# etherbotix_revB.net
KiCad netlist of a schematic drawn in EAGLE
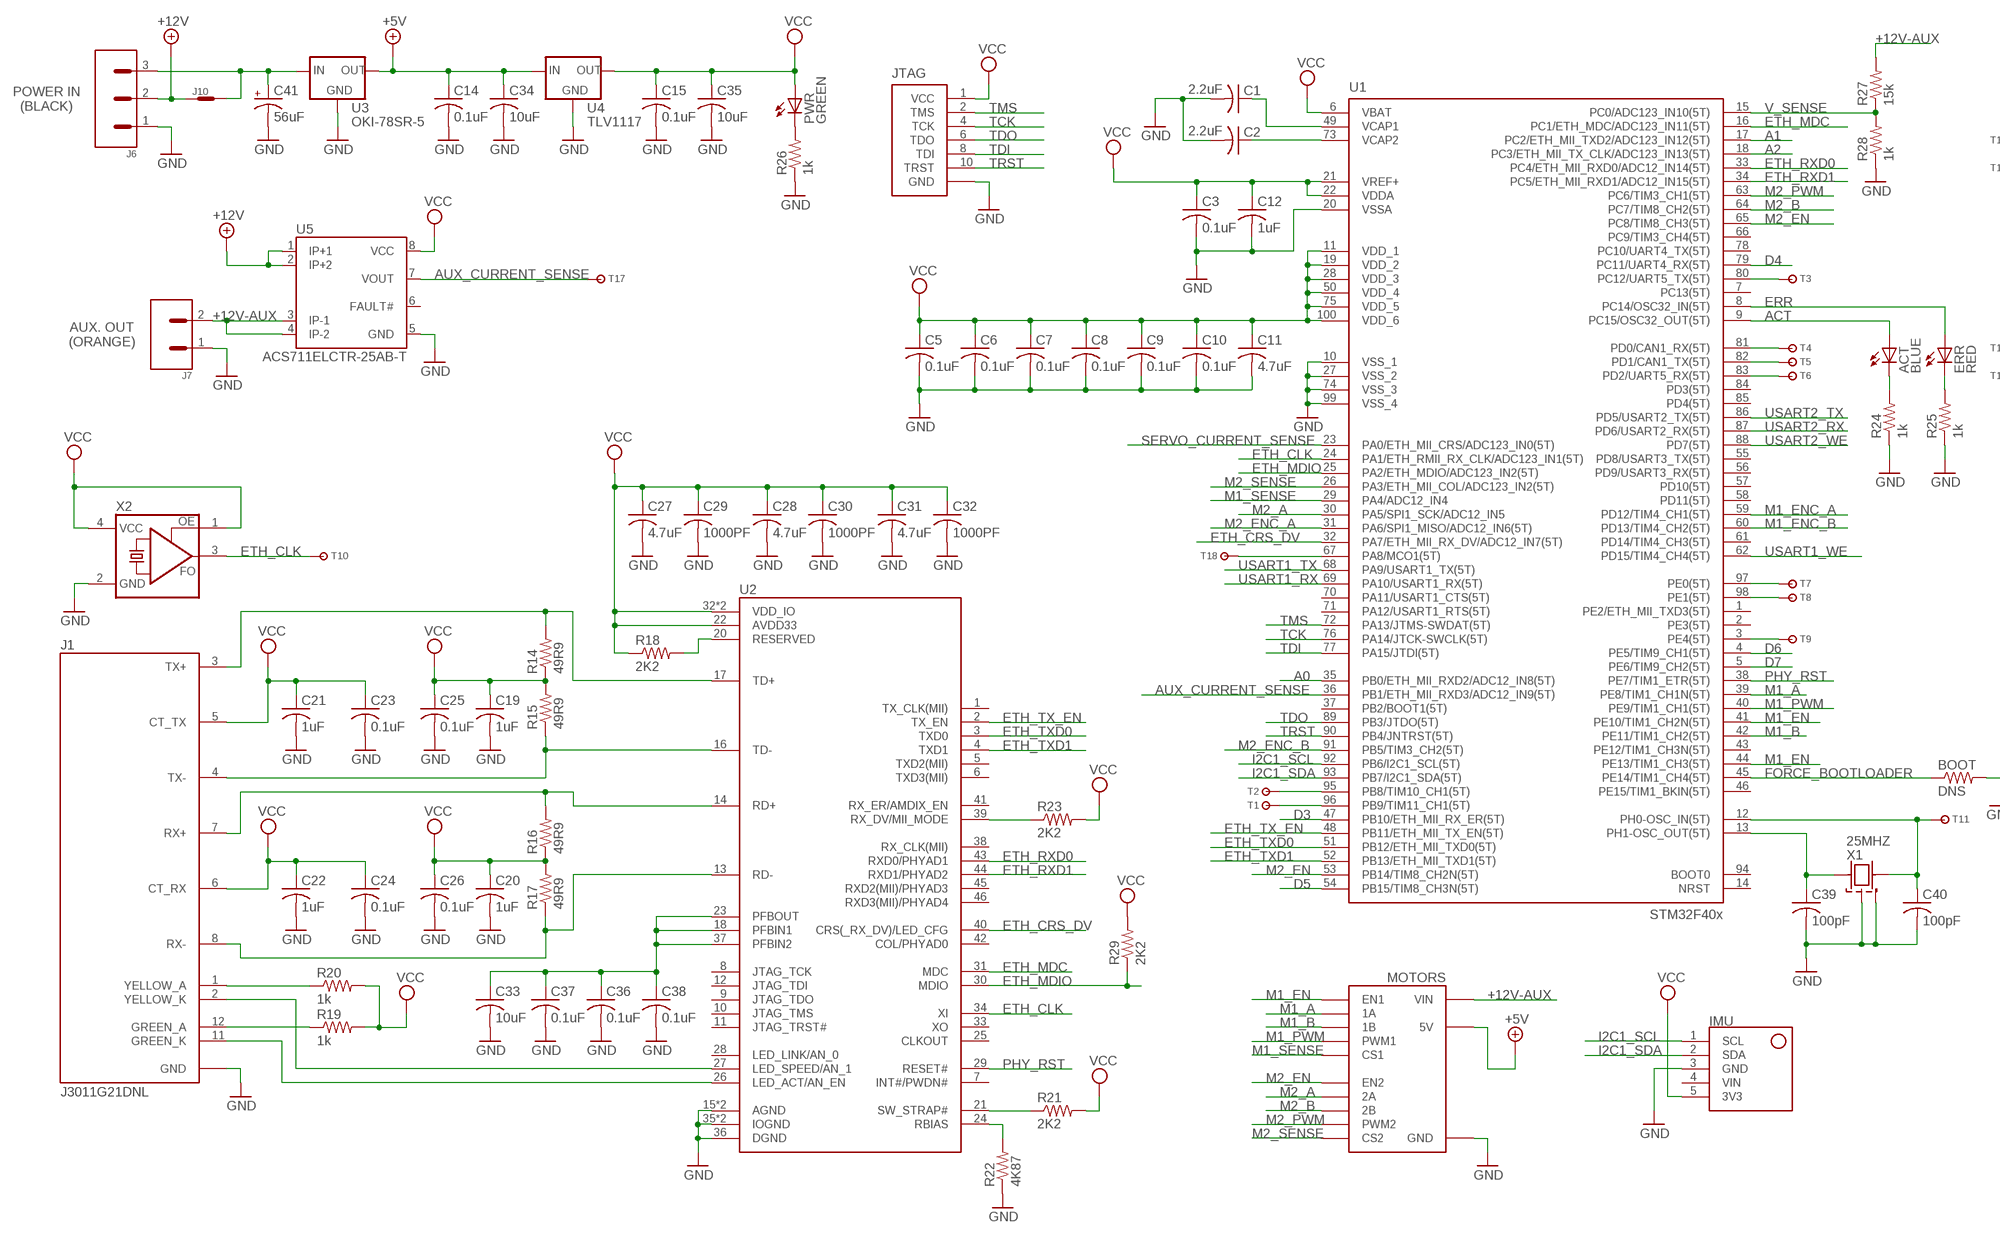
[diagram p0: schematic, sheet 1, part 1 of 2]
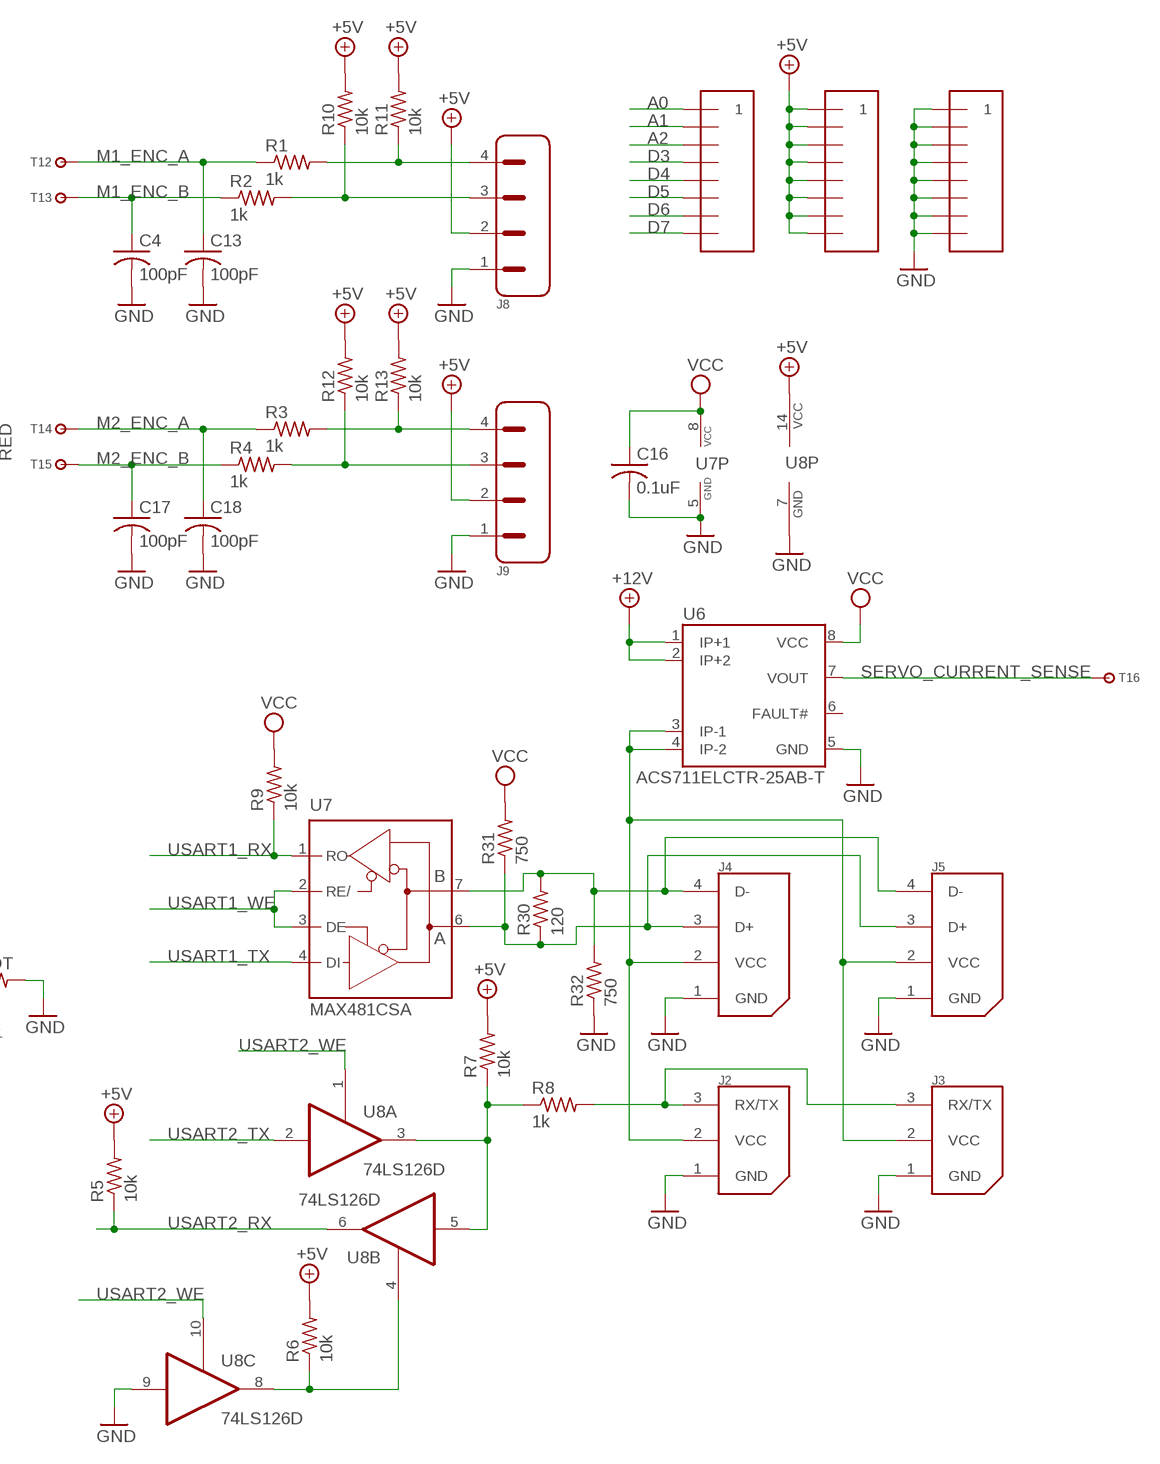
[diagram p1: schematic, sheet 1, part 2 of 2]

(export (version "E")
  (design (tool "Eeschema 10.0.6"))
  (components
    (comp (ref "ACT")
      (value "BLUE")
      (footprint "eagle-import:LED0603")
      (libsource (lib "eagle-import") (part "APT1608SGC"))
    )
    (comp (ref "BOOT")
      (value "DNS")
      (footprint "eagle-import:0603")
      (libsource (lib "eagle-import") (part "P1.00KHCT-ND"))
    )
    (comp (ref "C1")
      (value "2.2uF")
      (footprint "eagle-import:C0603")
      (libsource (lib "eagle-import") (part "C1608X5R1C225K"))
    )
    (comp (ref "C2")
      (value "2.2uF")
      (footprint "eagle-import:C0603")
      (libsource (lib "eagle-import") (part "C1608X5R1C225K"))
    )
    (comp (ref "C3")
      (value "0.1uF")
      (footprint "eagle-import:C0603")
      (libsource (lib "eagle-import") (part "C1608X7R1H104K"))
    )
    (comp (ref "C4")
      (value "100pF")
      (footprint "eagle-import:C0603")
      (libsource (lib "eagle-import") (part "C1608C0G1H101J"))
    )
    (comp (ref "C5")
      (value "0.1uF")
      (footprint "eagle-import:C0603")
      (libsource (lib "eagle-import") (part "C1608X7R1H104K"))
    )
    (comp (ref "C6")
      (value "0.1uF")
      (footprint "eagle-import:C0603")
      (libsource (lib "eagle-import") (part "C1608X7R1H104K"))
    )
    (comp (ref "C7")
      (value "0.1uF")
      (footprint "eagle-import:C0603")
      (libsource (lib "eagle-import") (part "C1608X7R1H104K"))
    )
    (comp (ref "C8")
      (value "0.1uF")
      (footprint "eagle-import:C0603")
      (libsource (lib "eagle-import") (part "C1608X7R1H104K"))
    )
    (comp (ref "C9")
      (value "0.1uF")
      (footprint "eagle-import:C0603")
      (libsource (lib "eagle-import") (part "C1608X7R1H104K"))
    )
    (comp (ref "C10")
      (value "0.1uF")
      (footprint "eagle-import:C0603")
      (libsource (lib "eagle-import") (part "C1608X7R1H104K"))
    )
    (comp (ref "C11")
      (value "4.7uF")
      (footprint "eagle-import:0603")
      (libsource (lib "eagle-import") (part "C1608X5R0J475K"))
    )
    (comp (ref "C12")
      (value "1uF")
      (footprint "eagle-import:C0603")
      (libsource (lib "eagle-import") (part "C1608X5R1H105M"))
    )
    (comp (ref "C13")
      (value "100pF")
      (footprint "eagle-import:C0603")
      (libsource (lib "eagle-import") (part "C1608C0G1H101J"))
    )
    (comp (ref "C14")
      (value "0.1uF")
      (footprint "eagle-import:C0603")
      (libsource (lib "eagle-import") (part "C1608X7R1H104K"))
    )
    (comp (ref "C15")
      (value "0.1uF")
      (footprint "eagle-import:C0603")
      (libsource (lib "eagle-import") (part "C1608X7R1H104K"))
    )
    (comp (ref "C16")
      (value "0.1uF")
      (footprint "eagle-import:C0603")
      (libsource (lib "eagle-import") (part "C1608X7R1H104K"))
    )
    (comp (ref "C17")
      (value "100pF")
      (footprint "eagle-import:C0603")
      (libsource (lib "eagle-import") (part "C1608C0G1H101J"))
    )
    (comp (ref "C18")
      (value "100pF")
      (footprint "eagle-import:C0603")
      (libsource (lib "eagle-import") (part "C1608C0G1H101J"))
    )
    (comp (ref "C19")
      (value "1uF")
      (footprint "eagle-import:C0603")
      (libsource (lib "eagle-import") (part "C1608X5R1H105M"))
    )
    (comp (ref "C20")
      (value "1uF")
      (footprint "eagle-import:C0603")
      (libsource (lib "eagle-import") (part "C1608X5R1H105M"))
    )
    (comp (ref "C21")
      (value "1uF")
      (footprint "eagle-import:C0603")
      (libsource (lib "eagle-import") (part "C1608X5R1H105M"))
    )
    (comp (ref "C22")
      (value "1uF")
      (footprint "eagle-import:C0603")
      (libsource (lib "eagle-import") (part "C1608X5R1H105M"))
    )
    (comp (ref "C23")
      (value "0.1uF")
      (footprint "eagle-import:C0603")
      (libsource (lib "eagle-import") (part "C1608X7R1H104K"))
    )
    (comp (ref "C24")
      (value "0.1uF")
      (footprint "eagle-import:C0603")
      (libsource (lib "eagle-import") (part "C1608X7R1H104K"))
    )
    (comp (ref "C25")
      (value "0.1uF")
      (footprint "eagle-import:C0603")
      (libsource (lib "eagle-import") (part "C1608X7R1H104K"))
    )
    (comp (ref "C26")
      (value "0.1uF")
      (footprint "eagle-import:C0603")
      (libsource (lib "eagle-import") (part "C1608X7R1H104K"))
    )
    (comp (ref "C27")
      (value "4.7uF")
      (footprint "eagle-import:0603")
      (libsource (lib "eagle-import") (part "C1608X5R0J475K"))
    )
    (comp (ref "C28")
      (value "4.7uF")
      (footprint "eagle-import:0603")
      (libsource (lib "eagle-import") (part "C1608X5R0J475K"))
    )
    (comp (ref "C29")
      (value "1000PF")
      (footprint "eagle-import:0603")
      (libsource (lib "eagle-import") (part "C1608X7R1H102K"))
    )
    (comp (ref "C30")
      (value "1000PF")
      (footprint "eagle-import:0603")
      (libsource (lib "eagle-import") (part "C1608X7R1H102K"))
    )
    (comp (ref "C31")
      (value "4.7uF")
      (footprint "eagle-import:0603")
      (libsource (lib "eagle-import") (part "C1608X5R0J475K"))
    )
    (comp (ref "C32")
      (value "1000PF")
      (footprint "eagle-import:0603")
      (libsource (lib "eagle-import") (part "C1608X7R1H102K"))
    )
    (comp (ref "C33")
      (value "10uF")
      (footprint "eagle-import:C0603")
      (libsource (lib "eagle-import") (part "C1608X5R0J106M"))
    )
    (comp (ref "C34")
      (value "10uF")
      (footprint "eagle-import:C0603")
      (libsource (lib "eagle-import") (part "C1608X5R0J106M"))
    )
    (comp (ref "C35")
      (value "10uF")
      (footprint "eagle-import:C0603")
      (libsource (lib "eagle-import") (part "C1608X5R0J106M"))
    )
    (comp (ref "C36")
      (value "0.1uF")
      (footprint "eagle-import:C0603")
      (libsource (lib "eagle-import") (part "C1608X7R1H104K"))
    )
    (comp (ref "C37")
      (value "0.1uF")
      (footprint "eagle-import:C0603")
      (libsource (lib "eagle-import") (part "C1608X7R1H104K"))
    )
    (comp (ref "C38")
      (value "0.1uF")
      (footprint "eagle-import:C0603")
      (libsource (lib "eagle-import") (part "C1608X7R1H104K"))
    )
    (comp (ref "C39")
      (value "100pF")
      (footprint "eagle-import:C0603")
      (libsource (lib "eagle-import") (part "C1608C0G1H101J"))
    )
    (comp (ref "C40")
      (value "100pF")
      (footprint "eagle-import:C0603")
      (libsource (lib "eagle-import") (part "C1608C0G1H101J"))
    )
    (comp (ref "C41")
      (value "56uF")
      (footprint "eagle-import:OSCON_SVPF_6.3MM")
      (libsource (lib "eagle-import") (part "25SVPF56M"))
    )
    (comp (ref "ERR")
      (value "RED")
      (footprint "eagle-import:LED0603")
      (libsource (lib "eagle-import") (part "APT1608SGC"))
    )
    (comp (ref "IMU")
      (value "MINI9IMU")
      (footprint "eagle-import:MINI9IMU")
      (libsource (lib "eagle-import") (part "MINI9IMU"))
    )
    (comp (ref "J1")
      (value "J3011G21DNL")
      (footprint "eagle-import:J3")
      (libsource (lib "eagle-import") (part "J3011G21DNL"))
    )
    (comp (ref "J2")
      (value "22-03-5035")
      (footprint "eagle-import:5267-3")
      (libsource (lib "eagle-import") (part "22-03-5035"))
    )
    (comp (ref "J3")
      (value "22-03-5035")
      (footprint "eagle-import:5267-3")
      (libsource (lib "eagle-import") (part "22-03-5035"))
    )
    (comp (ref "J4")
      (value "22-03-5045")
      (footprint "eagle-import:5267-4")
      (libsource (lib "eagle-import") (part "22-03-5045"))
    )
    (comp (ref "J5")
      (value "22-03-5045")
      (footprint "eagle-import:5267-4")
      (libsource (lib "eagle-import") (part "22-03-5045"))
    )
    (comp (ref "J6")
      (value "1760520000")
      (footprint "eagle-import:1760520000")
      (libsource (lib "eagle-import") (part "1760520000"))
    )
    (comp (ref "J7")
      (value "1760490000")
      (footprint "eagle-import:1760490000")
      (libsource (lib "eagle-import") (part "1760490000"))
    )
    (comp (ref "J8")
      (value "502443-0470")
      (footprint "eagle-import:502443-0470")
      (libsource (lib "eagle-import") (part "502443-0470"))
    )
    (comp (ref "J9")
      (value "502443-0470")
      (footprint "eagle-import:502443-0470")
      (libsource (lib "eagle-import") (part "502443-0470"))
    )
    (comp (ref "J10")
      (value "JUMPER")
      (footprint "eagle-import:J2")
      (libsource (lib "eagle-import") (part "JUMPER"))
    )
    (comp (ref "JTAG")
      (value "CORTEX_DEBUG-SHROUDED")
      (footprint "eagle-import:3220-10-0300-00")
      (libsource (lib "eagle-import") (part "CORTEX_DEBUG-SHROUDED"))
    )
    (comp (ref "MOTORS")
      (value "MD03A")
      (footprint "eagle-import:MD03A")
      (libsource (lib "eagle-import") (part "MD03A"))
    )
    (comp (ref "PWR")
      (value "GREEN")
      (footprint "eagle-import:LED0603")
      (libsource (lib "eagle-import") (part "APT1608SGC"))
    )
    (comp (ref "R1")
      (value "1k")
      (footprint "eagle-import:0603")
      (libsource (lib "eagle-import") (part "P1.00KHCT-ND"))
    )
    (comp (ref "R2")
      (value "1k")
      (footprint "eagle-import:0603")
      (libsource (lib "eagle-import") (part "P1.00KHCT-ND"))
    )
    (comp (ref "R3")
      (value "1k")
      (footprint "eagle-import:0603")
      (libsource (lib "eagle-import") (part "P1.00KHCT-ND"))
    )
    (comp (ref "R4")
      (value "1k")
      (footprint "eagle-import:0603")
      (libsource (lib "eagle-import") (part "P1.00KHCT-ND"))
    )
    (comp (ref "R5")
      (value "10k")
      (footprint "eagle-import:0603")
      (libsource (lib "eagle-import") (part "P10.0KHCT-ND"))
    )
    (comp (ref "R6")
      (value "10k")
      (footprint "eagle-import:0603")
      (libsource (lib "eagle-import") (part "P10.0KHCT-ND"))
    )
    (comp (ref "R7")
      (value "10k")
      (footprint "eagle-import:0603")
      (libsource (lib "eagle-import") (part "P10.0KHCT-ND"))
    )
    (comp (ref "R8")
      (value "1k")
      (footprint "eagle-import:0603")
      (libsource (lib "eagle-import") (part "P1.00KHCT-ND"))
    )
    (comp (ref "R9")
      (value "10k")
      (footprint "eagle-import:0603")
      (libsource (lib "eagle-import") (part "P10.0KHCT-ND"))
    )
    (comp (ref "R10")
      (value "10k")
      (footprint "eagle-import:0603")
      (libsource (lib "eagle-import") (part "P10.0KHCT-ND"))
    )
    (comp (ref "R11")
      (value "10k")
      (footprint "eagle-import:0603")
      (libsource (lib "eagle-import") (part "P10.0KHCT-ND"))
    )
    (comp (ref "R12")
      (value "10k")
      (footprint "eagle-import:0603")
      (libsource (lib "eagle-import") (part "P10.0KHCT-ND"))
    )
    (comp (ref "R13")
      (value "10k")
      (footprint "eagle-import:0603")
      (libsource (lib "eagle-import") (part "P10.0KHCT-ND"))
    )
    (comp (ref "R14")
      (value "49R9")
      (footprint "eagle-import:0603")
      (libsource (lib "eagle-import") (part "P49.9HCT-ND"))
    )
    (comp (ref "R15")
      (value "49R9")
      (footprint "eagle-import:0603")
      (libsource (lib "eagle-import") (part "P49.9HCT-ND"))
    )
    (comp (ref "R16")
      (value "49R9")
      (footprint "eagle-import:0603")
      (libsource (lib "eagle-import") (part "P49.9HCT-ND"))
    )
    (comp (ref "R17")
      (value "49R9")
      (footprint "eagle-import:0603")
      (libsource (lib "eagle-import") (part "P49.9HCT-ND"))
    )
    (comp (ref "R18")
      (value "2K2")
      (footprint "eagle-import:0603")
      (libsource (lib "eagle-import") (part "P2.20KHCT-ND"))
    )
    (comp (ref "R19")
      (value "1k")
      (footprint "eagle-import:0603")
      (libsource (lib "eagle-import") (part "P1.00KHCT-ND"))
    )
    (comp (ref "R20")
      (value "1k")
      (footprint "eagle-import:0603")
      (libsource (lib "eagle-import") (part "P1.00KHCT-ND"))
    )
    (comp (ref "R21")
      (value "2K2")
      (footprint "eagle-import:0603")
      (libsource (lib "eagle-import") (part "P2.20KHCT-ND"))
    )
    (comp (ref "R22")
      (value "4K87")
      (footprint "eagle-import:0603")
      (libsource (lib "eagle-import") (part "P4.87KHCT-ND"))
    )
    (comp (ref "R23")
      (value "2K2")
      (footprint "eagle-import:0603")
      (libsource (lib "eagle-import") (part "P2.20KHCT-ND"))
    )
    (comp (ref "R24")
      (value "1k")
      (footprint "eagle-import:0603")
      (libsource (lib "eagle-import") (part "P1.00KHCT-ND"))
    )
    (comp (ref "R25")
      (value "1k")
      (footprint "eagle-import:0603")
      (libsource (lib "eagle-import") (part "P1.00KHCT-ND"))
    )
    (comp (ref "R26")
      (value "1k")
      (footprint "eagle-import:0603")
      (libsource (lib "eagle-import") (part "P1.00KHCT-ND"))
    )
    (comp (ref "R27")
      (value "15k")
      (footprint "eagle-import:0603")
      (libsource (lib "eagle-import") (part "P15.0KHCT-ND"))
    )
    (comp (ref "R28")
      (value "1k")
      (footprint "eagle-import:0603")
      (libsource (lib "eagle-import") (part "P1.00KHCT-ND"))
    )
    (comp (ref "R29")
      (value "2K2")
      (footprint "eagle-import:0603")
      (libsource (lib "eagle-import") (part "P2.20KHCT-ND"))
    )
    (comp (ref "R30")
      (value "120")
      (footprint "eagle-import:0603")
      (libsource (lib "eagle-import") (part "P120HCT-ND"))
    )
    (comp (ref "R31")
      (value "750")
      (footprint "eagle-import:0603")
      (libsource (lib "eagle-import") (part "P750HCT-ND"))
    )
    (comp (ref "R32")
      (value "750")
      (footprint "eagle-import:0603")
      (libsource (lib "eagle-import") (part "P750HCT-ND"))
    )
    (comp (ref "T1")
      (value "TESTPAD")
      (footprint "eagle-import:TEST")
      (libsource (lib "eagle-import") (part "TESTPAD"))
    )
    (comp (ref "T2")
      (value "TESTPAD")
      (footprint "eagle-import:TEST")
      (libsource (lib "eagle-import") (part "TESTPAD"))
    )
    (comp (ref "T3")
      (value "TESTPAD")
      (footprint "eagle-import:TEST")
      (libsource (lib "eagle-import") (part "TESTPAD"))
    )
    (comp (ref "T4")
      (value "TESTPAD")
      (footprint "eagle-import:TEST")
      (libsource (lib "eagle-import") (part "TESTPAD"))
    )
    (comp (ref "T5")
      (value "TESTPAD")
      (footprint "eagle-import:TEST")
      (libsource (lib "eagle-import") (part "TESTPAD"))
    )
    (comp (ref "T6")
      (value "TESTPAD")
      (footprint "eagle-import:TEST")
      (libsource (lib "eagle-import") (part "TESTPAD"))
    )
    (comp (ref "T7")
      (value "TESTPAD")
      (footprint "eagle-import:TEST")
      (libsource (lib "eagle-import") (part "TESTPAD"))
    )
    (comp (ref "T8")
      (value "TESTPAD")
      (footprint "eagle-import:TEST")
      (libsource (lib "eagle-import") (part "TESTPAD"))
    )
    (comp (ref "T9")
      (value "TESTPAD")
      (footprint "eagle-import:TEST")
      (libsource (lib "eagle-import") (part "TESTPAD"))
    )
    (comp (ref "T10")
      (value "TESTPAD")
      (footprint "eagle-import:TEST")
      (libsource (lib "eagle-import") (part "TESTPAD"))
    )
    (comp (ref "T11")
      (value "TESTPAD")
      (footprint "eagle-import:TEST")
      (libsource (lib "eagle-import") (part "TESTPAD"))
    )
    (comp (ref "T12")
      (value "TESTPAD")
      (footprint "eagle-import:TEST")
      (libsource (lib "eagle-import") (part "TESTPAD"))
    )
    (comp (ref "T13")
      (value "TESTPAD")
      (footprint "eagle-import:TEST")
      (libsource (lib "eagle-import") (part "TESTPAD"))
    )
    (comp (ref "T14")
      (value "TESTPAD")
      (footprint "eagle-import:TEST")
      (libsource (lib "eagle-import") (part "TESTPAD"))
    )
    (comp (ref "T15")
      (value "TESTPAD")
      (footprint "eagle-import:TEST")
      (libsource (lib "eagle-import") (part "TESTPAD"))
    )
    (comp (ref "T16")
      (value "TESTPAD")
      (footprint "eagle-import:TEST")
      (libsource (lib "eagle-import") (part "TESTPAD"))
    )
    (comp (ref "T17")
      (value "TESTPAD")
      (footprint "eagle-import:TEST")
      (libsource (lib "eagle-import") (part "TESTPAD"))
    )
    (comp (ref "T18")
      (value "TESTPAD")
      (footprint "eagle-import:TEST")
      (libsource (lib "eagle-import") (part "TESTPAD"))
    )
    (comp (ref "U$1")
      (value "HEADER8")
      (footprint "eagle-import:1X8")
      (libsource (lib "eagle-import") (part "HEADER8"))
    )
    (comp (ref "U$2")
      (value "HEADER8")
      (footprint "eagle-import:1X8")
      (libsource (lib "eagle-import") (part "HEADER8"))
    )
    (comp (ref "U$3")
      (value "HEADER8")
      (footprint "eagle-import:1X8")
      (libsource (lib "eagle-import") (part "HEADER8"))
    )
    (comp (ref "U1")
      (value "STM32F407V")
      (footprint "eagle-import:TQFP100")
      (libsource (lib "eagle-import") (part "STM32F407V"))
    )
    (comp (ref "U2")
      (value "TLK110")
      (footprint "eagle-import:LQFP48")
      (libsource (lib "eagle-import") (part "TLK110"))
    )
    (comp (ref "U3")
      (value "OKI-78SR-5")
      (footprint "eagle-import:OKI-78SR")
      (fields (field (name "VOLTAGE") "5"))
      (libsource (lib "eagle-import") (part "OKI-78SR-W36-C-5/1.5"))
    )
    (comp (ref "U4")
      (value "TLV1117")
      (footprint "eagle-import:DPAK")
      (libsource (lib "eagle-import") (part "TLV1117-33IKVURG3KVU"))
    )
    (comp (ref "U5")
      (value "ACS711ELCTR-25AB-T")
      (footprint "eagle-import:SOIC8")
      (libsource (lib "eagle-import") (part "ACS711ELC?TR-25AB-T"))
    )
    (comp (ref "U6")
      (value "ACS711ELCTR-25AB-T")
      (footprint "eagle-import:SOIC8")
      (libsource (lib "eagle-import") (part "ACS711ELC?TR-25AB-T"))
    )
    (comp (ref "U7")
      (value "MAX481CSA")
      (footprint "eagle-import:SO08")
      (fields (field (name "MF") "MAXIM"))
      (libsource (lib "eagle-import") (part "MAX481CSA"))
    )
    (comp (ref "U8")
      (value "74LS126D")
      (footprint "eagle-import:SO14")
      (libsource (lib "eagle-import") (part "74126DLS"))
    )
    (comp (ref "X1")
      (value "25MHZ")
      (footprint "eagle-import:4LCC")
      (libsource (lib "eagle-import") (part "ABM3B-MHZ-B2-T25.000"))
    )
    (comp (ref "X2")
      (value "ASEMB-50.000MHZ-XY-T")
      (footprint "eagle-import:OSCILLATOR")
      (libsource (lib "eagle-import") (part "ASEMB-50.000MHZ-XY-T"))
    )
  )
  (nets
    (net (code "1") (name "+5V") (class "Default")
      (node (ref "C14") (pin "1") (pinfunction "1_1") (pintype "passive"))
      (node (ref "C34") (pin "1") (pinfunction "1_1") (pintype "passive"))
      (node (ref "J8") (pin "2") (pinfunction "2_2") (pintype "bidirectional"))
      (node (ref "J9") (pin "2") (pinfunction "2_2") (pintype "bidirectional"))
      (node (ref "MOTORS") (pin "5V") (pinfunction "5V_5V") (pintype "bidirectional"))
      (node (ref "R10") (pin "2") (pinfunction "2_2") (pintype "passive"))
      (node (ref "R11") (pin "2") (pinfunction "2_2") (pintype "passive"))
      (node (ref "R12") (pin "2") (pinfunction "2_2") (pintype "passive"))
      (node (ref "R13") (pin "2") (pinfunction "2_2") (pintype "passive"))
      (node (ref "R5") (pin "2") (pinfunction "2_2") (pintype "passive"))
      (node (ref "R6") (pin "2") (pinfunction "2_2") (pintype "passive"))
      (node (ref "R7") (pin "2") (pinfunction "2_2") (pintype "passive"))
      (node (ref "U$2") (pin "P$1") (pinfunction "1_P$1") (pintype "bidirectional"))
      (node (ref "U$2") (pin "P$2") (pinfunction "P$2_P$2") (pintype "bidirectional"))
      (node (ref "U$2") (pin "P$3") (pinfunction "P$3_P$3") (pintype "bidirectional"))
      (node (ref "U$2") (pin "P$4") (pinfunction "P$4_P$4") (pintype "bidirectional"))
      (node (ref "U$2") (pin "P$5") (pinfunction "P$5_P$5") (pintype "bidirectional"))
      (node (ref "U$2") (pin "P$6") (pinfunction "P$6_P$6") (pintype "bidirectional"))
      (node (ref "U$2") (pin "P$7") (pinfunction "P$7_P$7") (pintype "bidirectional"))
      (node (ref "U$2") (pin "P$8") (pinfunction "P$8_P$8") (pintype "bidirectional"))
      (node (ref "U3") (pin "P$3") (pinfunction "OUT_P$3") (pintype "passive"))
      (node (ref "U4") (pin "3") (pinfunction "IN_3") (pintype "input"))
      (node (ref "U8") (pin "14") (pinfunction "VCC_14") (pintype "power_in"))
    )
    (net (code "2") (name "+12V") (class "Default")
      (node (ref "J10") (pin "A") (pinfunction "A_A") (pintype "bidirectional"))
      (node (ref "J6") (pin "2") (pinfunction "2_2") (pintype "bidirectional"))
      (node (ref "U5") (pin "1") (pinfunction "IP+1_1") (pintype "bidirectional"))
      (node (ref "U5") (pin "2") (pinfunction "IP+2_2") (pintype "bidirectional"))
      (node (ref "U6") (pin "1") (pinfunction "IP+1_1") (pintype "bidirectional"))
      (node (ref "U6") (pin "2") (pinfunction "IP+2_2") (pintype "bidirectional"))
    )
    (net (code "3") (name "/+12V-AUX") (class "Default")
      (node (ref "J7") (pin "2") (pinfunction "2_2") (pintype "bidirectional"))
      (node (ref "MOTORS") (pin "VIN1") (pinfunction "VIN_VIN1") (pintype "bidirectional"))
      (node (ref "MOTORS") (pin "VIN2") (pinfunction "VIN_VIN2") (pintype "bidirectional"))
      (node (ref "R27") (pin "2") (pinfunction "2_2") (pintype "passive"))
      (node (ref "U5") (pin "3") (pinfunction "IP-1_3") (pintype "bidirectional"))
      (node (ref "U5") (pin "4") (pinfunction "IP-2_4") (pintype "bidirectional"))
    )
    (net (code "4") (name "/A0") (class "Default")
      (node (ref "U$1") (pin "P$1") (pinfunction "1_P$1") (pintype "bidirectional"))
      (node (ref "U1") (pin "35") (pinfunction "PB0/ETH_MII_RXD2/ADC12_IN8(5T)_35") (pintype "bidirectional"))
    )
    (net (code "5") (name "/A1") (class "Default")
      (node (ref "U$1") (pin "P$2") (pinfunction "P$2_P$2") (pintype "bidirectional"))
      (node (ref "U1") (pin "17") (pinfunction "PC2/ETH_MII_TXD2/ADC123_IN12(5T)_17") (pintype "bidirectional"))
    )
    (net (code "6") (name "/A2") (class "Default")
      (node (ref "U$1") (pin "P$3") (pinfunction "P$3_P$3") (pintype "bidirectional"))
      (node (ref "U1") (pin "18") (pinfunction "PC3/ETH_MII_TX_CLK/ADC123_IN13(5T)_18") (pintype "bidirectional"))
    )
    (net (code "7") (name "/ACT") (class "Default")
      (node (ref "ACT") (pin "A") (pinfunction "A_A") (pintype "passive"))
      (node (ref "U1") (pin "9") (pinfunction "PC15/OSC32_OUT(5T)_9") (pintype "bidirectional"))
    )
    (net (code "8") (name "/AUX_CURRENT_SENSE") (class "Default")
      (node (ref "T17") (pin "T") (pinfunction "1_T") (pintype "bidirectional"))
      (node (ref "U1") (pin "36") (pinfunction "PB1/ETH_MII_RXD3/ADC12_IN9(5T)_36") (pintype "bidirectional"))
      (node (ref "U5") (pin "7") (pinfunction "VOUT_7") (pintype "bidirectional"))
    )
    (net (code "9") (name "/D3") (class "Default")
      (node (ref "U$1") (pin "P$4") (pinfunction "P$4_P$4") (pintype "bidirectional"))
      (node (ref "U1") (pin "47") (pinfunction "PB10/ETH_MII_RX_ER(5T)_47") (pintype "bidirectional"))
    )
    (net (code "10") (name "/D4") (class "Default")
      (node (ref "U$1") (pin "P$5") (pinfunction "P$5_P$5") (pintype "bidirectional"))
      (node (ref "U1") (pin "79") (pinfunction "PC11/UART4_RX(5T)_79") (pintype "bidirectional"))
    )
    (net (code "11") (name "/D5") (class "Default")
      (node (ref "U$1") (pin "P$6") (pinfunction "P$6_P$6") (pintype "bidirectional"))
      (node (ref "U1") (pin "54") (pinfunction "PB15/TIM8_CH3N(5T)_54") (pintype "bidirectional"))
    )
    (net (code "12") (name "/D6") (class "Default")
      (node (ref "U$1") (pin "P$7") (pinfunction "P$7_P$7") (pintype "bidirectional"))
      (node (ref "U1") (pin "4") (pinfunction "PE5/TIM9_CH1(5T)_4") (pintype "bidirectional"))
    )
    (net (code "13") (name "/D7") (class "Default")
      (node (ref "U$1") (pin "P$8") (pinfunction "P$8_P$8") (pintype "bidirectional"))
      (node (ref "U1") (pin "5") (pinfunction "PE6/TIM9_CH2(5T)_5") (pintype "bidirectional"))
    )
    (net (code "14") (name "/ERR") (class "Default")
      (node (ref "ERR") (pin "A") (pinfunction "A_A") (pintype "passive"))
      (node (ref "U1") (pin "8") (pinfunction "PC14/OSC32_IN(5T)_8") (pintype "bidirectional"))
    )
    (net (code "15") (name "/ETH_CLK") (class "Default")
      (node (ref "T10") (pin "T") (pinfunction "1_T") (pintype "bidirectional"))
      (node (ref "U1") (pin "24") (pinfunction "PA1/ETH_RMII_RX_CLK/ADC123_IN1(5T)_24") (pintype "bidirectional"))
      (node (ref "U2") (pin "34") (pinfunction "XI_34") (pintype "bidirectional"))
      (node (ref "X2") (pin "3") (pinfunction "FO_3") (pintype "output"))
    )
    (net (code "16") (name "/ETH_CRS_DV") (class "Default")
      (node (ref "U1") (pin "32") (pinfunction "PA7/ETH_MII_RX_DV/ADC12_IN7(5T)_32") (pintype "bidirectional"))
      (node (ref "U2") (pin "40") (pinfunction "CRS(_RX_DV)/LED_CFG_40") (pintype "bidirectional"))
    )
    (net (code "17") (name "/ETH_MDC") (class "Default")
      (node (ref "U1") (pin "16") (pinfunction "PC1/ETH_MDC/ADC123_IN11(5T)_16") (pintype "bidirectional"))
      (node (ref "U2") (pin "31") (pinfunction "MDC_31") (pintype "bidirectional"))
    )
    (net (code "18") (name "/ETH_MDIO") (class "Default")
      (node (ref "R29") (pin "1") (pinfunction "1_1") (pintype "passive"))
      (node (ref "U1") (pin "25") (pinfunction "PA2/ETH_MDIO/ADC123_IN2(5T)_25") (pintype "bidirectional"))
      (node (ref "U2") (pin "30") (pinfunction "MDIO_30") (pintype "bidirectional"))
    )
    (net (code "19") (name "/ETH_RXD0") (class "Default")
      (node (ref "U1") (pin "33") (pinfunction "PC4/ETH_MII_RXD0/ADC12_IN14(5T)_33") (pintype "bidirectional"))
      (node (ref "U2") (pin "43") (pinfunction "RXD0/PHYAD1_43") (pintype "bidirectional"))
    )
    (net (code "20") (name "/ETH_RXD1") (class "Default")
      (node (ref "U1") (pin "34") (pinfunction "PC5/ETH_MII_RXD1/ADC12_IN15(5T)_34") (pintype "bidirectional"))
      (node (ref "U2") (pin "44") (pinfunction "RXD1/PHYAD2_44") (pintype "bidirectional"))
    )
    (net (code "21") (name "/ETH_TXD0") (class "Default")
      (node (ref "U1") (pin "51") (pinfunction "PB12/ETH_MII_TXD0(5T)_51") (pintype "bidirectional"))
      (node (ref "U2") (pin "3") (pinfunction "TXD0_3") (pintype "bidirectional"))
    )
    (net (code "22") (name "/ETH_TXD1") (class "Default")
      (node (ref "U1") (pin "52") (pinfunction "PB13/ETH_MII_TXD1(5T)_52") (pintype "bidirectional"))
      (node (ref "U2") (pin "4") (pinfunction "TXD1_4") (pintype "bidirectional"))
    )
    (net (code "23") (name "/ETH_TX_EN") (class "Default")
      (node (ref "U1") (pin "48") (pinfunction "PB11/ETH_MII_TX_EN(5T)_48") (pintype "bidirectional"))
      (node (ref "U2") (pin "2") (pinfunction "TX_EN_2") (pintype "bidirectional"))
    )
    (net (code "24") (name "/FORCE_BOOTLOADER") (class "Default")
      (node (ref "BOOT") (pin "1") (pinfunction "1_1") (pintype "passive"))
      (node (ref "U1") (pin "45") (pinfunction "PE14/TIM1_CH4(5T)_45") (pintype "bidirectional"))
    )
    (net (code "25") (name "/I2C1_SCL") (class "Default")
      (node (ref "IMU") (pin "1") (pinfunction "SCL_1") (pintype "bidirectional"))
      (node (ref "U1") (pin "92") (pinfunction "PB6/I2C1_SCL(5T)_92") (pintype "bidirectional"))
    )
    (net (code "26") (name "/I2C1_SDA") (class "Default")
      (node (ref "IMU") (pin "2") (pinfunction "SDA_2") (pintype "bidirectional"))
      (node (ref "U1") (pin "93") (pinfunction "PB7/I2C1_SDA(5T)_93") (pintype "bidirectional"))
    )
    (net (code "27") (name "/M1_A") (class "Default")
      (node (ref "MOTORS") (pin "1A") (pinfunction "1A_1A") (pintype "bidirectional"))
      (node (ref "U1") (pin "39") (pinfunction "PE8/TIM1_CH1N(5T)_39") (pintype "bidirectional"))
    )
    (net (code "28") (name "/M1_B") (class "Default")
      (node (ref "MOTORS") (pin "1B") (pinfunction "1B_1B") (pintype "bidirectional"))
      (node (ref "U1") (pin "42") (pinfunction "PE11/TIM1_CH2(5T)_42") (pintype "bidirectional"))
    )
    (net (code "29") (name "/M1_EN") (class "Default")
      (node (ref "MOTORS") (pin "EN1") (pinfunction "EN1_EN1") (pintype "bidirectional"))
      (node (ref "U1") (pin "41") (pinfunction "PE10/TIM1_CH2N(5T)_41") (pintype "bidirectional"))
      (node (ref "U1") (pin "44") (pinfunction "PE13/TIM1_CH3(5T)_44") (pintype "bidirectional"))
    )
    (net (code "30") (name "/M1_ENC_A") (class "Default")
      (node (ref "C13") (pin "1") (pinfunction "1_1") (pintype "passive"))
      (node (ref "R1") (pin "1") (pinfunction "1_1") (pintype "passive"))
      (node (ref "T12") (pin "T") (pinfunction "1_T") (pintype "bidirectional"))
      (node (ref "U1") (pin "59") (pinfunction "PD12/TIM4_CH1(5T)_59") (pintype "bidirectional"))
    )
    (net (code "31") (name "/M1_ENC_B") (class "Default")
      (node (ref "C4") (pin "1") (pinfunction "1_1") (pintype "passive"))
      (node (ref "R2") (pin "1") (pinfunction "1_1") (pintype "passive"))
      (node (ref "T13") (pin "T") (pinfunction "1_T") (pintype "bidirectional"))
      (node (ref "U1") (pin "60") (pinfunction "PD13/TIM4_CH2(5T)_60") (pintype "bidirectional"))
    )
    (net (code "32") (name "/M1_PWM") (class "Default")
      (node (ref "MOTORS") (pin "PWM1") (pinfunction "PWM1_PWM1") (pintype "bidirectional"))
      (node (ref "U1") (pin "40") (pinfunction "PE9/TIM1_CH1(5T)_40") (pintype "bidirectional"))
    )
    (net (code "33") (name "/M1_SENSE") (class "Default")
      (node (ref "MOTORS") (pin "CS1") (pinfunction "CS1_CS1") (pintype "bidirectional"))
      (node (ref "U1") (pin "29") (pinfunction "PA4/ADC12_IN4_29") (pintype "bidirectional"))
    )
    (net (code "34") (name "/M2_A") (class "Default")
      (node (ref "MOTORS") (pin "2A") (pinfunction "2A_2A") (pintype "bidirectional"))
      (node (ref "U1") (pin "30") (pinfunction "PA5/SPI1_SCK/ADC12_IN5_30") (pintype "bidirectional"))
    )
    (net (code "35") (name "/M2_B") (class "Default")
      (node (ref "MOTORS") (pin "2B") (pinfunction "2B_2B") (pintype "bidirectional"))
      (node (ref "U1") (pin "64") (pinfunction "PC7/TIM8_CH2(5T)_64") (pintype "bidirectional"))
    )
    (net (code "36") (name "/M2_EN") (class "Default")
      (node (ref "MOTORS") (pin "EN2") (pinfunction "EN2_EN2") (pintype "bidirectional"))
      (node (ref "U1") (pin "53") (pinfunction "PB14/TIM8_CH2N(5T)_53") (pintype "bidirectional"))
      (node (ref "U1") (pin "65") (pinfunction "PC8/TIM8_CH3(5T)_65") (pintype "bidirectional"))
    )
    (net (code "37") (name "/M2_ENC_A") (class "Default")
      (node (ref "C18") (pin "1") (pinfunction "1_1") (pintype "passive"))
      (node (ref "R3") (pin "1") (pinfunction "1_1") (pintype "passive"))
      (node (ref "T14") (pin "T") (pinfunction "1_T") (pintype "bidirectional"))
      (node (ref "U1") (pin "31") (pinfunction "PA6/SPI1_MISO/ADC12_IN6(5T)_31") (pintype "bidirectional"))
    )
    (net (code "38") (name "/M2_ENC_B") (class "Default")
      (node (ref "C17") (pin "1") (pinfunction "1_1") (pintype "passive"))
      (node (ref "R4") (pin "1") (pinfunction "1_1") (pintype "passive"))
      (node (ref "T15") (pin "T") (pinfunction "1_T") (pintype "bidirectional"))
      (node (ref "U1") (pin "91") (pinfunction "PB5/TIM3_CH2(5T)_91") (pintype "bidirectional"))
    )
    (net (code "39") (name "/M2_PWM") (class "Default")
      (node (ref "MOTORS") (pin "PWM2") (pinfunction "PWM2_PWM2") (pintype "bidirectional"))
      (node (ref "U1") (pin "63") (pinfunction "PC6/TIM3_CH1(5T)_63") (pintype "bidirectional"))
    )
    (net (code "40") (name "/M2_SENSE") (class "Default")
      (node (ref "MOTORS") (pin "CS2") (pinfunction "CS2_CS2") (pintype "bidirectional"))
      (node (ref "U1") (pin "26") (pinfunction "PA3/ETH_MII_COL/ADC123_IN2(5T)_26") (pintype "bidirectional"))
    )
    (net (code "41") (name "/PHY_RST") (class "Default")
      (node (ref "U1") (pin "38") (pinfunction "PE7/TIM1_ETR(5T)_38") (pintype "bidirectional"))
      (node (ref "U2") (pin "29") (pinfunction "RESET#_29") (pintype "bidirectional"))
    )
    (net (code "42") (name "/SERVO_CURRENT_SENSE") (class "Default")
      (node (ref "T16") (pin "T") (pinfunction "1_T") (pintype "bidirectional"))
      (node (ref "U1") (pin "23") (pinfunction "PA0/ETH_MII_CRS/ADC123_IN0(5T)_23") (pintype "bidirectional"))
      (node (ref "U6") (pin "7") (pinfunction "VOUT_7") (pintype "bidirectional"))
    )
    (net (code "43") (name "/TCK") (class "Default")
      (node (ref "JTAG") (pin "4") (pinfunction "TCK_4") (pintype "bidirectional"))
      (node (ref "U1") (pin "76") (pinfunction "PA14/JTCK-SWCLK(5T)_76") (pintype "bidirectional"))
    )
    (net (code "44") (name "/TDI") (class "Default")
      (node (ref "JTAG") (pin "8") (pinfunction "TDI_8") (pintype "bidirectional"))
      (node (ref "U1") (pin "77") (pinfunction "PA15/JTDI(5T)_77") (pintype "bidirectional"))
    )
    (net (code "45") (name "/TDO") (class "Default")
      (node (ref "JTAG") (pin "6") (pinfunction "TDO_6") (pintype "bidirectional"))
      (node (ref "U1") (pin "89") (pinfunction "PB3/JTDO(5T)_89") (pintype "bidirectional"))
    )
    (net (code "46") (name "/TMS") (class "Default")
      (node (ref "JTAG") (pin "2") (pinfunction "TMS_2") (pintype "bidirectional"))
      (node (ref "U1") (pin "72") (pinfunction "PA13/JTMS-SWDAT(5T)_72") (pintype "bidirectional"))
    )
    (net (code "47") (name "/TRST") (class "Default")
      (node (ref "JTAG") (pin "10") (pinfunction "TRST_10") (pintype "bidirectional"))
      (node (ref "U1") (pin "90") (pinfunction "PB4/JNTRST(5T)_90") (pintype "bidirectional"))
    )
    (net (code "48") (name "/USART1_RX") (class "Default")
      (node (ref "R9") (pin "1") (pinfunction "1_1") (pintype "passive"))
      (node (ref "U1") (pin "69") (pinfunction "PA10/USART1_RX(5T)_69") (pintype "bidirectional"))
      (node (ref "U7") (pin "1") (pinfunction "RO_1") (pintype "output"))
    )
    (net (code "49") (name "/USART1_TX") (class "Default")
      (node (ref "U1") (pin "68") (pinfunction "PA9/USART1_TX(5T)_68") (pintype "bidirectional"))
      (node (ref "U7") (pin "4") (pinfunction "DI_4") (pintype "input"))
    )
    (net (code "50") (name "/USART1_WE") (class "Default")
      (node (ref "U1") (pin "62") (pinfunction "PD15/TIM4_CH4(5T)_62") (pintype "bidirectional"))
      (node (ref "U7") (pin "2") (pinfunction "RE/_2") (pintype "input"))
      (node (ref "U7") (pin "3") (pinfunction "DE_3") (pintype "input"))
    )
    (net (code "51") (name "/USART2_RX") (class "Default")
      (node (ref "R5") (pin "1") (pinfunction "1_1") (pintype "passive"))
      (node (ref "U1") (pin "87") (pinfunction "PD6/USART2_RX(5T)_87") (pintype "bidirectional"))
      (node (ref "U8") (pin "6") (pinfunction "O_6") (pintype "output"))
    )
    (net (code "52") (name "/USART2_TX") (class "Default")
      (node (ref "U1") (pin "86") (pinfunction "PD5/USART2_TX(5T)_86") (pintype "bidirectional"))
      (node (ref "U8") (pin "2") (pinfunction "I_2") (pintype "input"))
    )
    (net (code "53") (name "/USART2_WE") (class "Default")
      (node (ref "U1") (pin "88") (pinfunction "PD7(5T)_88") (pintype "bidirectional"))
      (node (ref "U8") (pin "1") (pinfunction "OE_1") (pintype "input"))
      (node (ref "U8") (pin "10") (pinfunction "OE_10") (pintype "input"))
    )
    (net (code "54") (name "/V_SENSE") (class "Default")
      (node (ref "R27") (pin "1") (pinfunction "1_1") (pintype "passive"))
      (node (ref "R28") (pin "2") (pinfunction "2_2") (pintype "passive"))
      (node (ref "U1") (pin "15") (pinfunction "PC0/ADC123_IN10(5T)_15") (pintype "bidirectional"))
    )
    (net (code "55") (name "GND") (class "Default")
      (node (ref "BOOT") (pin "2") (pinfunction "2_2") (pintype "passive"))
      (node (ref "C1") (pin "2") (pinfunction "2_2") (pintype "passive"))
      (node (ref "C10") (pin "2") (pinfunction "2_2") (pintype "passive"))
      (node (ref "C11") (pin "2") (pinfunction "2_2") (pintype "passive"))
      (node (ref "C12") (pin "2") (pinfunction "2_2") (pintype "passive"))
      (node (ref "C13") (pin "2") (pinfunction "2_2") (pintype "passive"))
      (node (ref "C14") (pin "2") (pinfunction "2_2") (pintype "passive"))
      (node (ref "C15") (pin "2") (pinfunction "2_2") (pintype "passive"))
      (node (ref "C16") (pin "2") (pinfunction "2_2") (pintype "passive"))
      (node (ref "C17") (pin "2") (pinfunction "2_2") (pintype "passive"))
      (node (ref "C18") (pin "2") (pinfunction "2_2") (pintype "passive"))
      (node (ref "C19") (pin "2") (pinfunction "2_2") (pintype "passive"))
      (node (ref "C2") (pin "2") (pinfunction "2_2") (pintype "passive"))
      (node (ref "C20") (pin "2") (pinfunction "2_2") (pintype "passive"))
      (node (ref "C21") (pin "2") (pinfunction "2_2") (pintype "passive"))
      (node (ref "C22") (pin "2") (pinfunction "2_2") (pintype "passive"))
      (node (ref "C23") (pin "2") (pinfunction "2_2") (pintype "passive"))
      (node (ref "C24") (pin "2") (pinfunction "2_2") (pintype "passive"))
      (node (ref "C25") (pin "2") (pinfunction "2_2") (pintype "passive"))
      (node (ref "C26") (pin "2") (pinfunction "2_2") (pintype "passive"))
      (node (ref "C27") (pin "2") (pinfunction "2_2") (pintype "passive"))
      (node (ref "C28") (pin "2") (pinfunction "2_2") (pintype "passive"))
      (node (ref "C29") (pin "2") (pinfunction "2_2") (pintype "passive"))
      (node (ref "C3") (pin "2") (pinfunction "2_2") (pintype "passive"))
      (node (ref "C30") (pin "2") (pinfunction "2_2") (pintype "passive"))
      (node (ref "C31") (pin "2") (pinfunction "2_2") (pintype "passive"))
      (node (ref "C32") (pin "2") (pinfunction "2_2") (pintype "passive"))
      (node (ref "C33") (pin "2") (pinfunction "2_2") (pintype "passive"))
      (node (ref "C34") (pin "2") (pinfunction "2_2") (pintype "passive"))
      (node (ref "C35") (pin "2") (pinfunction "2_2") (pintype "passive"))
      (node (ref "C36") (pin "2") (pinfunction "2_2") (pintype "passive"))
      (node (ref "C37") (pin "2") (pinfunction "2_2") (pintype "passive"))
      (node (ref "C38") (pin "2") (pinfunction "2_2") (pintype "passive"))
      (node (ref "C39") (pin "2") (pinfunction "2_2") (pintype "passive"))
      (node (ref "C4") (pin "2") (pinfunction "2_2") (pintype "passive"))
      (node (ref "C40") (pin "2") (pinfunction "2_2") (pintype "passive"))
      (node (ref "C41") (pin "-") (pinfunction "-_-") (pintype "passive"))
      (node (ref "C5") (pin "2") (pinfunction "2_2") (pintype "passive"))
      (node (ref "C6") (pin "2") (pinfunction "2_2") (pintype "passive"))
      (node (ref "C7") (pin "2") (pinfunction "2_2") (pintype "passive"))
      (node (ref "C8") (pin "2") (pinfunction "2_2") (pintype "passive"))
      (node (ref "C9") (pin "2") (pinfunction "2_2") (pintype "passive"))
      (node (ref "IMU") (pin "3") (pinfunction "GND_3") (pintype "bidirectional"))
      (node (ref "J1") (pin "10") (pinfunction "GND_10") (pintype "bidirectional"))
      (node (ref "J1") (pin "9") (pinfunction "GND_9") (pintype "bidirectional"))
      (node (ref "J1") (pin "A") (pinfunction "GND_A") (pintype "bidirectional"))
      (node (ref "J1") (pin "B") (pinfunction "GND_B") (pintype "bidirectional"))
      (node (ref "J2") (pin "1") (pinfunction "GND_1") (pintype "bidirectional"))
      (node (ref "J3") (pin "1") (pinfunction "GND_1") (pintype "bidirectional"))
      (node (ref "J4") (pin "1") (pinfunction "GND_1") (pintype "bidirectional"))
      (node (ref "J5") (pin "1") (pinfunction "GND_1") (pintype "bidirectional"))
      (node (ref "J6") (pin "1") (pinfunction "1_1") (pintype "bidirectional"))
      (node (ref "J7") (pin "1") (pinfunction "1_1") (pintype "bidirectional"))
      (node (ref "J8") (pin "1") (pinfunction "1_1") (pintype "bidirectional"))
      (node (ref "J9") (pin "1") (pinfunction "1_1") (pintype "bidirectional"))
      (node (ref "JTAG") (pin "3") (pinfunction "GND_3") (pintype "bidirectional"))
      (node (ref "JTAG") (pin "5") (pinfunction "GND_5") (pintype "bidirectional"))
      (node (ref "JTAG") (pin "9") (pinfunction "GND_9") (pintype "bidirectional"))
      (node (ref "MOTORS") (pin "GND1") (pinfunction "GND_GND1") (pintype "bidirectional"))
      (node (ref "MOTORS") (pin "GND2") (pinfunction "GND_GND2") (pintype "bidirectional"))
      (node (ref "R22") (pin "1") (pinfunction "1_1") (pintype "passive"))
      (node (ref "R24") (pin "1") (pinfunction "1_1") (pintype "passive"))
      (node (ref "R25") (pin "1") (pinfunction "1_1") (pintype "passive"))
      (node (ref "R26") (pin "1") (pinfunction "1_1") (pintype "passive"))
      (node (ref "R28") (pin "1") (pinfunction "1_1") (pintype "passive"))
      (node (ref "R32") (pin "1") (pinfunction "1_1") (pintype "passive"))
      (node (ref "U$3") (pin "P$1") (pinfunction "1_P$1") (pintype "bidirectional"))
      (node (ref "U$3") (pin "P$2") (pinfunction "P$2_P$2") (pintype "bidirectional"))
      (node (ref "U$3") (pin "P$3") (pinfunction "P$3_P$3") (pintype "bidirectional"))
      (node (ref "U$3") (pin "P$4") (pinfunction "P$4_P$4") (pintype "bidirectional"))
      (node (ref "U$3") (pin "P$5") (pinfunction "P$5_P$5") (pintype "bidirectional"))
      (node (ref "U$3") (pin "P$6") (pinfunction "P$6_P$6") (pintype "bidirectional"))
      (node (ref "U$3") (pin "P$7") (pinfunction "P$7_P$7") (pintype "bidirectional"))
      (node (ref "U$3") (pin "P$8") (pinfunction "P$8_P$8") (pintype "bidirectional"))
      (node (ref "U1") (pin "10") (pinfunction "VSS_1_10") (pintype "bidirectional"))
      (node (ref "U1") (pin "20") (pinfunction "VSSA_20") (pintype "bidirectional"))
      (node (ref "U1") (pin "27") (pinfunction "VSS_2_27") (pintype "bidirectional"))
      (node (ref "U1") (pin "74") (pinfunction "VSS_3_74") (pintype "bidirectional"))
      (node (ref "U1") (pin "99") (pinfunction "VSS_4_99") (pintype "bidirectional"))
      (node (ref "U2") (pin "15") (pinfunction "AGND_15") (pintype "bidirectional"))
      (node (ref "U2") (pin "19") (pinfunction "AGND_19") (pintype "bidirectional"))
      (node (ref "U2") (pin "35") (pinfunction "IOGND_35") (pintype "bidirectional"))
      (node (ref "U2") (pin "36") (pinfunction "DGND_36") (pintype "bidirectional"))
      (node (ref "U2") (pin "47") (pinfunction "IOGND_47") (pintype "bidirectional"))
      (node (ref "U3") (pin "P$2") (pinfunction "GND_P$2") (pintype "input"))
      (node (ref "U4") (pin "1") (pinfunction "GND_1") (pintype "input"))
      (node (ref "U5") (pin "5") (pinfunction "GND_5") (pintype "bidirectional"))
      (node (ref "U6") (pin "5") (pinfunction "GND_5") (pintype "bidirectional"))
      (node (ref "U7") (pin "5") (pinfunction "GND_5") (pintype "power_in"))
      (node (ref "U8") (pin "7") (pinfunction "GND_7") (pintype "power_in"))
      (node (ref "U8") (pin "9") (pinfunction "I_9") (pintype "input"))
      (node (ref "X1") (pin "2") (pinfunction "G1_2") (pintype "bidirectional"))
      (node (ref "X1") (pin "4") (pinfunction "G2_4") (pintype "bidirectional"))
      (node (ref "X2") (pin "2") (pinfunction "GND_2") (pintype "power_in"))
    )
    (net (code "56") (name "Net-(ACT-PadC)") (class "Default")
      (node (ref "ACT") (pin "C") (pinfunction "C_C") (pintype "passive"))
      (node (ref "R24") (pin "2") (pinfunction "2_2") (pintype "passive"))
    )
    (net (code "57") (name "Net-(ERR-PadC)") (class "Default")
      (node (ref "ERR") (pin "C") (pinfunction "C_C") (pintype "passive"))
      (node (ref "R25") (pin "2") (pinfunction "2_2") (pintype "passive"))
    )
    (net (code "58") (name "Net-(J1-GREEN_A)") (class "Default")
      (node (ref "J1") (pin "12") (pinfunction "GREEN_A_12") (pintype "bidirectional"))
      (node (ref "R19") (pin "1") (pinfunction "1_1") (pintype "passive"))
    )
    (net (code "59") (name "Net-(J1-GREEN_K)") (class "Default")
      (node (ref "J1") (pin "11") (pinfunction "GREEN_K_11") (pintype "bidirectional"))
      (node (ref "U2") (pin "26") (pinfunction "LED_ACT/AN_EN_26") (pintype "bidirectional"))
    )
    (net (code "60") (name "Net-(J1-RX+)") (class "Default")
      (node (ref "J1") (pin "7") (pinfunction "RX+_7") (pintype "bidirectional"))
      (node (ref "R16") (pin "2") (pinfunction "2_2") (pintype "passive"))
      (node (ref "U2") (pin "14") (pinfunction "RD+_14") (pintype "bidirectional"))
    )
    (net (code "61") (name "Net-(J1-RX-)") (class "Default")
      (node (ref "J1") (pin "8") (pinfunction "RX-_8") (pintype "bidirectional"))
      (node (ref "R17") (pin "1") (pinfunction "1_1") (pintype "passive"))
      (node (ref "U2") (pin "13") (pinfunction "RD-_13") (pintype "bidirectional"))
    )
    (net (code "62") (name "Net-(J1-TX+)") (class "Default")
      (node (ref "J1") (pin "3") (pinfunction "TX+_3") (pintype "bidirectional"))
      (node (ref "R14") (pin "2") (pinfunction "2_2") (pintype "passive"))
      (node (ref "U2") (pin "17") (pinfunction "TD+_17") (pintype "bidirectional"))
    )
    (net (code "63") (name "Net-(J1-TX-)") (class "Default")
      (node (ref "J1") (pin "4") (pinfunction "TX-_4") (pintype "bidirectional"))
      (node (ref "R15") (pin "1") (pinfunction "1_1") (pintype "passive"))
      (node (ref "U2") (pin "16") (pinfunction "TD-_16") (pintype "bidirectional"))
    )
    (net (code "64") (name "Net-(J1-YELLOW_A)") (class "Default")
      (node (ref "J1") (pin "1") (pinfunction "YELLOW_A_1") (pintype "bidirectional"))
      (node (ref "R20") (pin "1") (pinfunction "1_1") (pintype "passive"))
    )
    (net (code "65") (name "Net-(J1-YELLOW_K)") (class "Default")
      (node (ref "J1") (pin "2") (pinfunction "YELLOW_K_2") (pintype "bidirectional"))
      (node (ref "U2") (pin "27") (pinfunction "LED_SPEED/AN_1_27") (pintype "bidirectional"))
    )
    (net (code "66") (name "Net-(J2-RX{slash}TX)") (class "Default")
      (node (ref "J2") (pin "3") (pinfunction "RX/TX_3") (pintype "bidirectional"))
      (node (ref "J3") (pin "3") (pinfunction "RX/TX_3") (pintype "bidirectional"))
      (node (ref "R8") (pin "2") (pinfunction "2_2") (pintype "passive"))
    )
    (net (code "67") (name "Net-(J2-VCC)") (class "Default")
      (node (ref "J2") (pin "2") (pinfunction "VCC_2") (pintype "bidirectional"))
      (node (ref "J3") (pin "2") (pinfunction "VCC_2") (pintype "bidirectional"))
      (node (ref "J4") (pin "2") (pinfunction "VCC_2") (pintype "bidirectional"))
      (node (ref "J5") (pin "2") (pinfunction "VCC_2") (pintype "bidirectional"))
      (node (ref "U6") (pin "3") (pinfunction "IP-1_3") (pintype "bidirectional"))
      (node (ref "U6") (pin "4") (pinfunction "IP-2_4") (pintype "bidirectional"))
    )
    (net (code "68") (name "Net-(J4-D+)") (class "Default")
      (node (ref "J4") (pin "3") (pinfunction "D+_3") (pintype "bidirectional"))
      (node (ref "J5") (pin "3") (pinfunction "D+_3") (pintype "bidirectional"))
      (node (ref "R30") (pin "1") (pinfunction "1_1") (pintype "passive"))
      (node (ref "R31") (pin "1") (pinfunction "1_1") (pintype "passive"))
      (node (ref "U7") (pin "6") (pinfunction "A_6") (pintype "passive"))
    )
    (net (code "69") (name "Net-(J4-D-)") (class "Default")
      (node (ref "J4") (pin "4") (pinfunction "D-_4") (pintype "bidirectional"))
      (node (ref "J5") (pin "4") (pinfunction "D-_4") (pintype "bidirectional"))
      (node (ref "R30") (pin "2") (pinfunction "2_2") (pintype "passive"))
      (node (ref "R32") (pin "2") (pinfunction "2_2") (pintype "passive"))
      (node (ref "U7") (pin "7") (pinfunction "B_7") (pintype "passive"))
    )
    (net (code "70") (name "Net-(J8-Pad3)") (class "Default")
      (node (ref "J8") (pin "3") (pinfunction "3_3") (pintype "bidirectional"))
      (node (ref "R10") (pin "1") (pinfunction "1_1") (pintype "passive"))
      (node (ref "R2") (pin "2") (pinfunction "2_2") (pintype "passive"))
    )
    (net (code "71") (name "Net-(J8-Pad4)") (class "Default")
      (node (ref "J8") (pin "4") (pinfunction "4_4") (pintype "bidirectional"))
      (node (ref "R1") (pin "2") (pinfunction "2_2") (pintype "passive"))
      (node (ref "R11") (pin "1") (pinfunction "1_1") (pintype "passive"))
    )
    (net (code "72") (name "Net-(J9-Pad3)") (class "Default")
      (node (ref "J9") (pin "3") (pinfunction "3_3") (pintype "bidirectional"))
      (node (ref "R12") (pin "1") (pinfunction "1_1") (pintype "passive"))
      (node (ref "R4") (pin "2") (pinfunction "2_2") (pintype "passive"))
    )
    (net (code "73") (name "Net-(J9-Pad4)") (class "Default")
      (node (ref "J9") (pin "4") (pinfunction "4_4") (pintype "bidirectional"))
      (node (ref "R13") (pin "1") (pinfunction "1_1") (pintype "passive"))
      (node (ref "R3") (pin "2") (pinfunction "2_2") (pintype "passive"))
    )
    (net (code "74") (name "Net-(PWR-PadC)") (class "Default")
      (node (ref "PWR") (pin "C") (pinfunction "C_C") (pintype "passive"))
      (node (ref "R26") (pin "2") (pinfunction "2_2") (pintype "passive"))
    )
    (net (code "75") (name "Net-(T1-1)") (class "Default")
      (node (ref "T1") (pin "T") (pinfunction "1_T") (pintype "bidirectional"))
      (node (ref "U1") (pin "96") (pinfunction "PB9/TIM11_CH1(5T)_96") (pintype "bidirectional"))
    )
    (net (code "76") (name "Net-(T2-1)") (class "Default")
      (node (ref "T2") (pin "T") (pinfunction "1_T") (pintype "bidirectional"))
      (node (ref "U1") (pin "95") (pinfunction "PB8/TIM10_CH1(5T)_95") (pintype "bidirectional"))
    )
    (net (code "77") (name "Net-(T3-1)") (class "Default")
      (node (ref "T3") (pin "T") (pinfunction "1_T") (pintype "bidirectional"))
      (node (ref "U1") (pin "80") (pinfunction "PC12/UART5_TX(5T)_80") (pintype "bidirectional"))
    )
    (net (code "78") (name "Net-(T4-1)") (class "Default")
      (node (ref "T4") (pin "T") (pinfunction "1_T") (pintype "bidirectional"))
      (node (ref "U1") (pin "81") (pinfunction "PD0/CAN1_RX(5T)_81") (pintype "bidirectional"))
    )
    (net (code "79") (name "Net-(T5-1)") (class "Default")
      (node (ref "T5") (pin "T") (pinfunction "1_T") (pintype "bidirectional"))
      (node (ref "U1") (pin "82") (pinfunction "PD1/CAN1_TX(5T)_82") (pintype "bidirectional"))
    )
    (net (code "80") (name "Net-(T6-1)") (class "Default")
      (node (ref "T6") (pin "T") (pinfunction "1_T") (pintype "bidirectional"))
      (node (ref "U1") (pin "83") (pinfunction "PD2/UART5_RX(5T)_83") (pintype "bidirectional"))
    )
    (net (code "81") (name "Net-(T7-1)") (class "Default")
      (node (ref "T7") (pin "T") (pinfunction "1_T") (pintype "bidirectional"))
      (node (ref "U1") (pin "97") (pinfunction "PE0(5T)_97") (pintype "bidirectional"))
    )
    (net (code "82") (name "Net-(T8-1)") (class "Default")
      (node (ref "T8") (pin "T") (pinfunction "1_T") (pintype "bidirectional"))
      (node (ref "U1") (pin "98") (pinfunction "PE1(5T)_98") (pintype "bidirectional"))
    )
    (net (code "83") (name "Net-(T9-1)") (class "Default")
      (node (ref "T9") (pin "T") (pinfunction "1_T") (pintype "bidirectional"))
      (node (ref "U1") (pin "3") (pinfunction "PE4(5T)_3") (pintype "bidirectional"))
    )
    (net (code "84") (name "Net-(T11-1)") (class "Default")
      (node (ref "C40") (pin "1") (pinfunction "1_1") (pintype "passive"))
      (node (ref "T11") (pin "T") (pinfunction "1_T") (pintype "bidirectional"))
      (node (ref "U1") (pin "12") (pinfunction "PH0-OSC_IN(5T)_12") (pintype "bidirectional"))
      (node (ref "X1") (pin "3") (pinfunction "P$2_3") (pintype "bidirectional"))
    )
    (net (code "85") (name "Net-(T18-1)") (class "Default")
      (node (ref "T18") (pin "T") (pinfunction "1_T") (pintype "bidirectional"))
      (node (ref "U1") (pin "67") (pinfunction "PA8/MCO1(5T)_67") (pintype "bidirectional"))
    )
    (net (code "86") (name "Net-(U1-PH1-OSC_OUT(5T))") (class "Default")
      (node (ref "C39") (pin "1") (pinfunction "1_1") (pintype "passive"))
      (node (ref "U1") (pin "13") (pinfunction "PH1-OSC_OUT(5T)_13") (pintype "bidirectional"))
      (node (ref "X1") (pin "1") (pinfunction "P$1_1") (pintype "bidirectional"))
    )
    (net (code "87") (name "Net-(U1-VCAP1)") (class "Default")
      (node (ref "C1") (pin "1") (pinfunction "1_1") (pintype "passive"))
      (node (ref "U1") (pin "49") (pinfunction "VCAP1_49") (pintype "bidirectional"))
    )
    (net (code "88") (name "Net-(U1-VCAP2)") (class "Default")
      (node (ref "C2") (pin "1") (pinfunction "1_1") (pintype "passive"))
      (node (ref "U1") (pin "73") (pinfunction "VCAP2_73") (pintype "bidirectional"))
    )
    (net (code "89") (name "Net-(U2-PFBIN1)") (class "Default")
      (node (ref "C33") (pin "1") (pinfunction "1_1") (pintype "passive"))
      (node (ref "C36") (pin "1") (pinfunction "1_1") (pintype "passive"))
      (node (ref "C37") (pin "1") (pinfunction "1_1") (pintype "passive"))
      (node (ref "C38") (pin "1") (pinfunction "1_1") (pintype "passive"))
      (node (ref "U2") (pin "18") (pinfunction "PFBIN1_18") (pintype "bidirectional"))
      (node (ref "U2") (pin "23") (pinfunction "PFBOUT_23") (pintype "bidirectional"))
      (node (ref "U2") (pin "37") (pinfunction "PFBIN2_37") (pintype "bidirectional"))
    )
    (net (code "90") (name "Net-(U2-RBIAS)") (class "Default")
      (node (ref "R22") (pin "2") (pinfunction "2_2") (pintype "passive"))
      (node (ref "U2") (pin "24") (pinfunction "RBIAS_24") (pintype "bidirectional"))
    )
    (net (code "91") (name "Net-(U2-RESERVED)") (class "Default")
      (node (ref "R18") (pin "2") (pinfunction "2_2") (pintype "passive"))
      (node (ref "U2") (pin "20") (pinfunction "RESERVED_20") (pintype "bidirectional"))
    )
    (net (code "92") (name "Net-(U2-RX_DV{slash}MII_MODE)") (class "Default")
      (node (ref "R23") (pin "1") (pinfunction "1_1") (pintype "passive"))
      (node (ref "U2") (pin "39") (pinfunction "RX_DV/MII_MODE_39") (pintype "bidirectional"))
    )
    (net (code "93") (name "Net-(U2-SW_STRAP#)") (class "Default")
      (node (ref "R21") (pin "1") (pinfunction "1_1") (pintype "passive"))
      (node (ref "U2") (pin "21") (pinfunction "SW_STRAP#_21") (pintype "bidirectional"))
    )
    (net (code "94") (name "Net-(U3-IN)") (class "Default")
      (node (ref "C41") (pin "+") (pinfunction "+_+") (pintype "passive"))
      (node (ref "J10") (pin "B") (pinfunction "B_B") (pintype "bidirectional"))
      (node (ref "J6") (pin "3") (pinfunction "3_3") (pintype "bidirectional"))
      (node (ref "U3") (pin "P$1") (pinfunction "IN_P$1") (pintype "input"))
    )
    (net (code "95") (name "Net-(U8A-O)") (class "Default")
      (node (ref "R7") (pin "1") (pinfunction "1_1") (pintype "passive"))
      (node (ref "R8") (pin "1") (pinfunction "1_1") (pintype "passive"))
      (node (ref "U8") (pin "3") (pinfunction "O_3") (pintype "output"))
      (node (ref "U8") (pin "5") (pinfunction "I_5") (pintype "input"))
    )
    (net (code "96") (name "Net-(U8B-OE)") (class "Default")
      (node (ref "R6") (pin "1") (pinfunction "1_1") (pintype "passive"))
      (node (ref "U8") (pin "4") (pinfunction "OE_4") (pintype "input"))
      (node (ref "U8") (pin "8") (pinfunction "O_8") (pintype "output"))
    )
    (net (code "97") (name "VCC") (class "Default")
      (node (ref "C10") (pin "1") (pinfunction "1_1") (pintype "passive"))
      (node (ref "C11") (pin "1") (pinfunction "1_1") (pintype "passive"))
      (node (ref "C12") (pin "1") (pinfunction "1_1") (pintype "passive"))
      (node (ref "C15") (pin "1") (pinfunction "1_1") (pintype "passive"))
      (node (ref "C16") (pin "1") (pinfunction "1_1") (pintype "passive"))
      (node (ref "C19") (pin "1") (pinfunction "1_1") (pintype "passive"))
      (node (ref "C20") (pin "1") (pinfunction "1_1") (pintype "passive"))
      (node (ref "C21") (pin "1") (pinfunction "1_1") (pintype "passive"))
      (node (ref "C22") (pin "1") (pinfunction "1_1") (pintype "passive"))
      (node (ref "C23") (pin "1") (pinfunction "1_1") (pintype "passive"))
      (node (ref "C24") (pin "1") (pinfunction "1_1") (pintype "passive"))
      (node (ref "C25") (pin "1") (pinfunction "1_1") (pintype "passive"))
      (node (ref "C26") (pin "1") (pinfunction "1_1") (pintype "passive"))
      (node (ref "C27") (pin "1") (pinfunction "1_1") (pintype "passive"))
      (node (ref "C28") (pin "1") (pinfunction "1_1") (pintype "passive"))
      (node (ref "C29") (pin "1") (pinfunction "1_1") (pintype "passive"))
      (node (ref "C3") (pin "1") (pinfunction "1_1") (pintype "passive"))
      (node (ref "C30") (pin "1") (pinfunction "1_1") (pintype "passive"))
      (node (ref "C31") (pin "1") (pinfunction "1_1") (pintype "passive"))
      (node (ref "C32") (pin "1") (pinfunction "1_1") (pintype "passive"))
      (node (ref "C35") (pin "1") (pinfunction "1_1") (pintype "passive"))
      (node (ref "C5") (pin "1") (pinfunction "1_1") (pintype "passive"))
      (node (ref "C6") (pin "1") (pinfunction "1_1") (pintype "passive"))
      (node (ref "C7") (pin "1") (pinfunction "1_1") (pintype "passive"))
      (node (ref "C8") (pin "1") (pinfunction "1_1") (pintype "passive"))
      (node (ref "C9") (pin "1") (pinfunction "1_1") (pintype "passive"))
      (node (ref "IMU") (pin "5") (pinfunction "3V3_5") (pintype "bidirectional"))
      (node (ref "J1") (pin "5") (pinfunction "CT_TX_5") (pintype "bidirectional"))
      (node (ref "J1") (pin "6") (pinfunction "CT_RX_6") (pintype "bidirectional"))
      (node (ref "JTAG") (pin "1") (pinfunction "VCC_1") (pintype "bidirectional"))
      (node (ref "PWR") (pin "A") (pinfunction "A_A") (pintype "passive"))
      (node (ref "R14") (pin "1") (pinfunction "1_1") (pintype "passive"))
      (node (ref "R15") (pin "2") (pinfunction "2_2") (pintype "passive"))
      (node (ref "R16") (pin "1") (pinfunction "1_1") (pintype "passive"))
      (node (ref "R17") (pin "2") (pinfunction "2_2") (pintype "passive"))
      (node (ref "R18") (pin "1") (pinfunction "1_1") (pintype "passive"))
      (node (ref "R19") (pin "2") (pinfunction "2_2") (pintype "passive"))
      (node (ref "R20") (pin "2") (pinfunction "2_2") (pintype "passive"))
      (node (ref "R21") (pin "2") (pinfunction "2_2") (pintype "passive"))
      (node (ref "R23") (pin "2") (pinfunction "2_2") (pintype "passive"))
      (node (ref "R29") (pin "2") (pinfunction "2_2") (pintype "passive"))
      (node (ref "R31") (pin "2") (pinfunction "2_2") (pintype "passive"))
      (node (ref "R9") (pin "2") (pinfunction "2_2") (pintype "passive"))
      (node (ref "U1") (pin "100") (pinfunction "VDD_6_100") (pintype "bidirectional"))
      (node (ref "U1") (pin "11") (pinfunction "VDD_1_11") (pintype "bidirectional"))
      (node (ref "U1") (pin "19") (pinfunction "VDD_2_19") (pintype "bidirectional"))
      (node (ref "U1") (pin "21") (pinfunction "VREF+_21") (pintype "bidirectional"))
      (node (ref "U1") (pin "22") (pinfunction "VDDA_22") (pintype "bidirectional"))
      (node (ref "U1") (pin "28") (pinfunction "VDD_3_28") (pintype "bidirectional"))
      (node (ref "U1") (pin "50") (pinfunction "VDD_4_50") (pintype "bidirectional"))
      (node (ref "U1") (pin "6") (pinfunction "VBAT_6") (pintype "bidirectional"))
      (node (ref "U1") (pin "75") (pinfunction "VDD_5_75") (pintype "bidirectional"))
      (node (ref "U2") (pin "22") (pinfunction "AVDD33_22") (pintype "bidirectional"))
      (node (ref "U2") (pin "32") (pinfunction "VDD_IO_32") (pintype "bidirectional"))
      (node (ref "U2") (pin "48") (pinfunction "VDD_IO_48") (pintype "bidirectional"))
      (node (ref "U4") (pin "4") (pinfunction "OUT_4") (pintype "passive"))
      (node (ref "U5") (pin "8") (pinfunction "VCC_8") (pintype "bidirectional"))
      (node (ref "U6") (pin "8") (pinfunction "VCC_8") (pintype "bidirectional"))
      (node (ref "U7") (pin "8") (pinfunction "VCC_8") (pintype "power_in"))
      (node (ref "X2") (pin "1") (pinfunction "OE_1") (pintype "input"))
      (node (ref "X2") (pin "4") (pinfunction "VCC_4") (pintype "power_in"))
    )
    (net (code "98") (name "unconnected-(IMU-VIN-Pad4)") (class "Default")
      (node (ref "IMU") (pin "4") (pinfunction "VIN_4") (pintype "bidirectional"))
    )
    (net (code "99") (name "unconnected-(U1-BOOT0-Pad94)") (class "Default")
      (node (ref "U1") (pin "94") (pinfunction "BOOT0_94") (pintype "bidirectional"))
    )
    (net (code "100") (name "unconnected-(U1-NRST-Pad14)") (class "Default")
      (node (ref "U1") (pin "14") (pinfunction "NRST_14") (pintype "bidirectional"))
    )
    (net (code "101") (name "unconnected-(U1-PA11{slash}USART1_CTS(5T)-Pad70)") (class "Default")
      (node (ref "U1") (pin "70") (pinfunction "PA11/USART1_CTS(5T)_70") (pintype "bidirectional"))
    )
    (net (code "102") (name "unconnected-(U1-PA12{slash}USART1_RTS(5T)-Pad71)") (class "Default")
      (node (ref "U1") (pin "71") (pinfunction "PA12/USART1_RTS(5T)_71") (pintype "bidirectional"))
    )
    (net (code "103") (name "unconnected-(U1-PB2{slash}BOOT1(5T)-Pad37)") (class "Default")
      (node (ref "U1") (pin "37") (pinfunction "PB2/BOOT1(5T)_37") (pintype "bidirectional"))
    )
    (net (code "104") (name "unconnected-(U1-PC9{slash}TIM3_CH4(5T)-Pad66)") (class "Default")
      (node (ref "U1") (pin "66") (pinfunction "PC9/TIM3_CH4(5T)_66") (pintype "bidirectional"))
    )
    (net (code "105") (name "unconnected-(U1-PC10{slash}UART4_TX(5T)-Pad78)") (class "Default")
      (node (ref "U1") (pin "78") (pinfunction "PC10/UART4_TX(5T)_78") (pintype "bidirectional"))
    )
    (net (code "106") (name "unconnected-(U1-PC13(5T)-Pad7)") (class "Default")
      (node (ref "U1") (pin "7") (pinfunction "PC13(5T)_7") (pintype "bidirectional"))
    )
    (net (code "107") (name "unconnected-(U1-PD3(5T)-Pad84)") (class "Default")
      (node (ref "U1") (pin "84") (pinfunction "PD3(5T)_84") (pintype "bidirectional"))
    )
    (net (code "108") (name "unconnected-(U1-PD4(5T)-Pad85)") (class "Default")
      (node (ref "U1") (pin "85") (pinfunction "PD4(5T)_85") (pintype "bidirectional"))
    )
    (net (code "109") (name "unconnected-(U1-PD8{slash}USART3_TX(5T)-Pad55)") (class "Default")
      (node (ref "U1") (pin "55") (pinfunction "PD8/USART3_TX(5T)_55") (pintype "bidirectional"))
    )
    (net (code "110") (name "unconnected-(U1-PD9{slash}USART3_RX(5T)-Pad56)") (class "Default")
      (node (ref "U1") (pin "56") (pinfunction "PD9/USART3_RX(5T)_56") (pintype "bidirectional"))
    )
    (net (code "111") (name "unconnected-(U1-PD10(5T)-Pad57)") (class "Default")
      (node (ref "U1") (pin "57") (pinfunction "PD10(5T)_57") (pintype "bidirectional"))
    )
    (net (code "112") (name "unconnected-(U1-PD11(5T)-Pad58)") (class "Default")
      (node (ref "U1") (pin "58") (pinfunction "PD11(5T)_58") (pintype "bidirectional"))
    )
    (net (code "113") (name "unconnected-(U1-PD14{slash}TIM4_CH3(5T)-Pad61)") (class "Default")
      (node (ref "U1") (pin "61") (pinfunction "PD14/TIM4_CH3(5T)_61") (pintype "bidirectional"))
    )
    (net (code "114") (name "unconnected-(U1-PE2{slash}ETH_MII_TXD3(5T)-Pad1)") (class "Default")
      (node (ref "U1") (pin "1") (pinfunction "PE2/ETH_MII_TXD3(5T)_1") (pintype "bidirectional"))
    )
    (net (code "115") (name "unconnected-(U1-PE3(5T)-Pad2)") (class "Default")
      (node (ref "U1") (pin "2") (pinfunction "PE3(5T)_2") (pintype "bidirectional"))
    )
    (net (code "116") (name "unconnected-(U1-PE12{slash}TIM1_CH3N(5T)-Pad43)") (class "Default")
      (node (ref "U1") (pin "43") (pinfunction "PE12/TIM1_CH3N(5T)_43") (pintype "bidirectional"))
    )
    (net (code "117") (name "unconnected-(U1-PE15{slash}TIM1_BKIN(5T)-Pad46)") (class "Default")
      (node (ref "U1") (pin "46") (pinfunction "PE15/TIM1_BKIN(5T)_46") (pintype "bidirectional"))
    )
    (net (code "118") (name "unconnected-(U2-CLKOUT-Pad25)") (class "Default")
      (node (ref "U2") (pin "25") (pinfunction "CLKOUT_25") (pintype "bidirectional"))
    )
    (net (code "119") (name "unconnected-(U2-COL{slash}PHYAD0-Pad42)") (class "Default")
      (node (ref "U2") (pin "42") (pinfunction "COL/PHYAD0_42") (pintype "bidirectional"))
    )
    (net (code "120") (name "unconnected-(U2-INT#{slash}PWDN#-Pad7)") (class "Default")
      (node (ref "U2") (pin "7") (pinfunction "INT#/PWDN#_7") (pintype "bidirectional"))
    )
    (net (code "121") (name "unconnected-(U2-JTAG_TCK-Pad8)") (class "Default")
      (node (ref "U2") (pin "8") (pinfunction "JTAG_TCK_8") (pintype "bidirectional"))
    )
    (net (code "122") (name "unconnected-(U2-JTAG_TDI-Pad12)") (class "Default")
      (node (ref "U2") (pin "12") (pinfunction "JTAG_TDI_12") (pintype "bidirectional"))
    )
    (net (code "123") (name "unconnected-(U2-JTAG_TDO-Pad9)") (class "Default")
      (node (ref "U2") (pin "9") (pinfunction "JTAG_TDO_9") (pintype "bidirectional"))
    )
    (net (code "124") (name "unconnected-(U2-JTAG_TMS-Pad10)") (class "Default")
      (node (ref "U2") (pin "10") (pinfunction "JTAG_TMS_10") (pintype "bidirectional"))
    )
    (net (code "125") (name "unconnected-(U2-JTAG_TRST#-Pad11)") (class "Default")
      (node (ref "U2") (pin "11") (pinfunction "JTAG_TRST#_11") (pintype "bidirectional"))
    )
    (net (code "126") (name "unconnected-(U2-LED_LINK{slash}AN_0-Pad28)") (class "Default")
      (node (ref "U2") (pin "28") (pinfunction "LED_LINK/AN_0_28") (pintype "bidirectional"))
    )
    (net (code "127") (name "unconnected-(U2-RXD2(MII){slash}PHYAD3-Pad45)") (class "Default")
      (node (ref "U2") (pin "45") (pinfunction "RXD2(MII)/PHYAD3_45") (pintype "bidirectional"))
    )
    (net (code "128") (name "unconnected-(U2-RXD3(MII){slash}PHYAD4-Pad46)") (class "Default")
      (node (ref "U2") (pin "46") (pinfunction "RXD3(MII)/PHYAD4_46") (pintype "bidirectional"))
    )
    (net (code "129") (name "unconnected-(U2-RX_CLK(MII)-Pad38)") (class "Default")
      (node (ref "U2") (pin "38") (pinfunction "RX_CLK(MII)_38") (pintype "bidirectional"))
    )
    (net (code "130") (name "unconnected-(U2-RX_ER{slash}AMDIX_EN-Pad41)") (class "Default")
      (node (ref "U2") (pin "41") (pinfunction "RX_ER/AMDIX_EN_41") (pintype "bidirectional"))
    )
    (net (code "131") (name "unconnected-(U2-TXD2(MII)-Pad5)") (class "Default")
      (node (ref "U2") (pin "5") (pinfunction "TXD2(MII)_5") (pintype "bidirectional"))
    )
    (net (code "132") (name "unconnected-(U2-TXD3(MII)-Pad6)") (class "Default")
      (node (ref "U2") (pin "6") (pinfunction "TXD3(MII)_6") (pintype "bidirectional"))
    )
    (net (code "133") (name "unconnected-(U2-TX_CLK(MII)-Pad1)") (class "Default")
      (node (ref "U2") (pin "1") (pinfunction "TX_CLK(MII)_1") (pintype "bidirectional"))
    )
    (net (code "134") (name "unconnected-(U2-XO-Pad33)") (class "Default")
      (node (ref "U2") (pin "33") (pinfunction "XO_33") (pintype "bidirectional"))
    )
    (net (code "135") (name "unconnected-(U5-FAULT#-Pad6)") (class "Default")
      (node (ref "U5") (pin "6") (pinfunction "FAULT#_6") (pintype "bidirectional"))
    )
    (net (code "136") (name "unconnected-(U6-FAULT#-Pad6)") (class "Default")
      (node (ref "U6") (pin "6") (pinfunction "FAULT#_6") (pintype "bidirectional"))
    )
  )
)
